# brick_i2c_3axis_adxl345.net
KiCad netlist of a schematic drawn in EAGLE
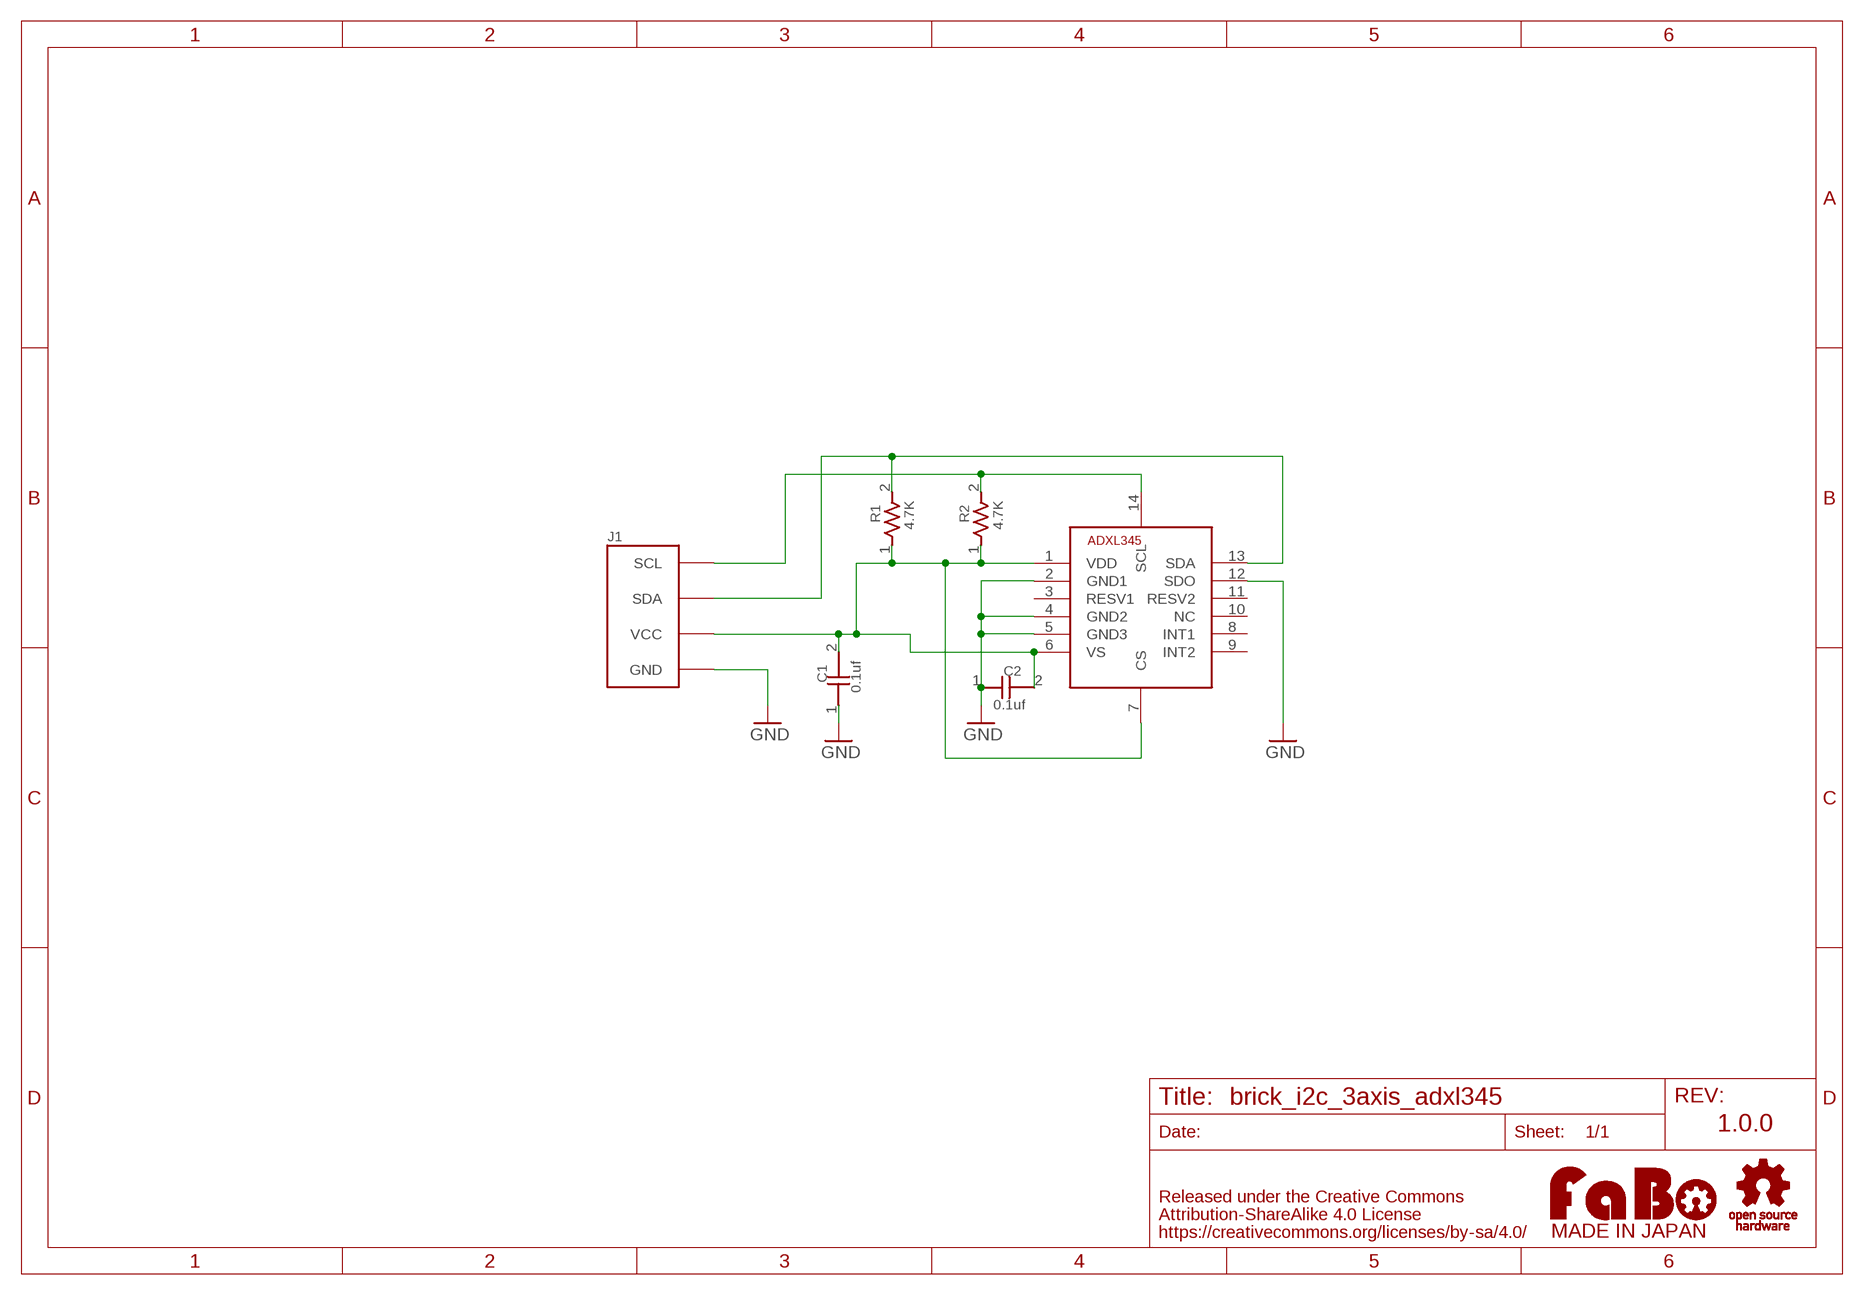
[diagram p0: schematic, sheet 1]

(export (version "E")
  (design (tool "Eeschema 10.0.6"))
  (components
    (comp (ref "C1")
      (value "0.1uf")
      (footprint "eagle-import:0603")
      (libsource (lib "eagle-import") (part "CAPACITOR0603"))
    )
    (comp (ref "C2")
      (value "0.1uf")
      (footprint "eagle-import:0603")
      (libsource (lib "eagle-import") (part "CAPACITOR0603"))
    )
    (comp (ref "J1")
      (value "BRICK_I2C")
      (footprint "eagle-import:BRICK_I2C")
      (libsource (lib "eagle-import") (part "BRICK_I2C"))
    )
    (comp (ref "R1")
      (value "4.7K")
      (footprint "eagle-import:0603")
      (libsource (lib "eagle-import") (part "RESISTOR0603"))
    )
    (comp (ref "R2")
      (value "4.7K")
      (footprint "eagle-import:0603")
      (libsource (lib "eagle-import") (part "RESISTOR0603"))
    )
    (comp (ref "U$2")
      (value "ANALOGDEVICES-ADXL345")
      (footprint "eagle-import:ANALOGDEVICES-ADXL345")
      (libsource (lib "eagle-import") (part "ANALOGDEVICES-ADXL345"))
    )
    (comp (ref "U$3")
      (value "LOGO_OSHW_T-M")
      (footprint "eagle-import:LOGO_OSHW_T_M")
      (libsource (lib "eagle-import") (part "LOGO_OSHW_T-M"))
    )
    (comp (ref "U$4")
      (value "LOGO_FABO-M")
      (footprint "eagle-import:LOGO_FABO_M")
      (libsource (lib "eagle-import") (part "LOGO_FABO-M"))
    )
  )
  (nets
    (net (code "1") (name "GND") (class "Default")
      (node (ref "C1") (pin "1") (pinfunction "1_1") (pintype "passive"))
      (node (ref "C2") (pin "1") (pinfunction "1_1") (pintype "passive"))
      (node (ref "J1") (pin "GND") (pinfunction "GND_GND") (pintype "bidirectional"))
      (node (ref "U$2") (pin "12") (pinfunction "SDO_12") (pintype "bidirectional"))
      (node (ref "U$2") (pin "2") (pinfunction "GND1_2") (pintype "bidirectional"))
      (node (ref "U$2") (pin "4") (pinfunction "GND2_4") (pintype "bidirectional"))
      (node (ref "U$2") (pin "5") (pinfunction "GND3_5") (pintype "bidirectional"))
    )
    (net (code "2") (name "Net-(U$2-CS)") (class "Default")
      (node (ref "C1") (pin "2") (pinfunction "2_2") (pintype "passive"))
      (node (ref "C2") (pin "2") (pinfunction "2_2") (pintype "passive"))
      (node (ref "J1") (pin "VCC") (pinfunction "VCC_VCC") (pintype "bidirectional"))
      (node (ref "R1") (pin "1") (pinfunction "1_1") (pintype "passive"))
      (node (ref "R2") (pin "1") (pinfunction "1_1") (pintype "passive"))
      (node (ref "U$2") (pin "1") (pinfunction "VDD_1") (pintype "bidirectional"))
      (node (ref "U$2") (pin "6") (pinfunction "VS_6") (pintype "bidirectional"))
      (node (ref "U$2") (pin "7") (pinfunction "CS_7") (pintype "bidirectional"))
    )
    (net (code "3") (name "Net-(U$2-SCL)") (class "Default")
      (node (ref "J1") (pin "SCL") (pinfunction "SCL_SCL") (pintype "bidirectional"))
      (node (ref "R2") (pin "2") (pinfunction "2_2") (pintype "passive"))
      (node (ref "U$2") (pin "14") (pinfunction "SCL_14") (pintype "bidirectional"))
    )
    (net (code "4") (name "Net-(U$2-SDA)") (class "Default")
      (node (ref "J1") (pin "SDA") (pinfunction "SDA_SDA") (pintype "bidirectional"))
      (node (ref "R1") (pin "2") (pinfunction "2_2") (pintype "passive"))
      (node (ref "U$2") (pin "13") (pinfunction "SDA_13") (pintype "bidirectional"))
    )
    (net (code "5") (name "unconnected-(U$2-INT1-Pad8)") (class "Default")
      (node (ref "U$2") (pin "8") (pinfunction "INT1_8") (pintype "bidirectional"))
    )
    (net (code "6") (name "unconnected-(U$2-INT2-Pad9)") (class "Default")
      (node (ref "U$2") (pin "9") (pinfunction "INT2_9") (pintype "bidirectional"))
    )
    (net (code "7") (name "unconnected-(U$2-NC-Pad10)") (class "Default")
      (node (ref "U$2") (pin "10") (pinfunction "NC_10") (pintype "bidirectional"))
    )
    (net (code "8") (name "unconnected-(U$2-RESV1-Pad3)") (class "Default")
      (node (ref "U$2") (pin "3") (pinfunction "RESV1_3") (pintype "bidirectional"))
    )
    (net (code "9") (name "unconnected-(U$2-RESV2-Pad11)") (class "Default")
      (node (ref "U$2") (pin "11") (pinfunction "RESV2_11") (pintype "bidirectional"))
    )
  )
)
